# USB.net
KiCad netlist of a schematic drawn in Altium Designer
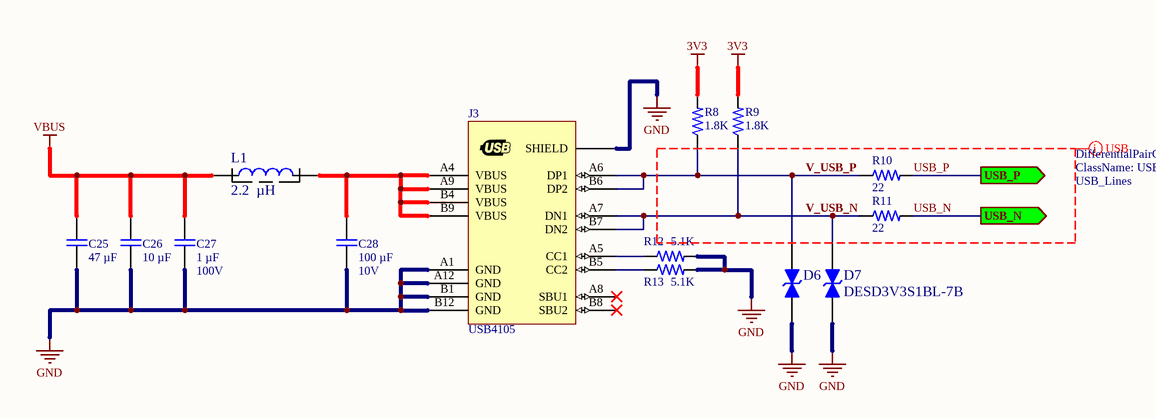
[diagram p0: USB.SchDoc]

(export (version "E")
  (design (tool "Eeschema 10.0.6"))
  (components
    (comp (ref "C25")
      (value "47 µF")
      (footprint "MergenElektronik_Capacitors_Ceramics_SMDs_1206_M_NS")
      (description "Mergen Elektronik - Capacitors - Ceramics - SMDs - 1206 - 47 µF - 25V")
      (fields (field (name "MANUFACTURER") "TDK Corporation") (field (name "TOLERANCE") "±20%"))
      (libsource (lib "MergenElektronik_Capacitors_Ceramics_SMDs") (part "MergenElektronik_Capacitors_Ceramic_SMDs_47µF_25V"))
    )
    (comp (ref "C26")
      (value "10 µF")
      (footprint "MergenElektronik_Capacitors_Ceramics_SMDs_0603_M_NS")
      (description "Mergen Elektronik - Capacitors - Ceramics - SMDs - 0603 - 10 µF - 25V")
      (fields (field (name "MANUFACTURER") "Murata Electronics") (field (name "TOLERANCE") "±20%"))
      (libsource (lib "MergenElektronik_Capacitors_Ceramics_SMDs") (part "MergenElektronik_Capacitors_Ceramic_SMDs_10µF_25V"))
    )
    (comp (ref "C27")
      (value "1 µF")
      (footprint "MergenElektronik_Capacitors_Ceramics_SMDs_1206_M_NS")
      (description "Mergen Elektronik - Capacitors - Ceramics - SMDs - 1206 - 1 µF - 100V")
      (fields
        (field (name "MANUFACTURER") "Samsung Electro-Mechanics")
        (field (name "TOLERANCE") "±10%")
        (field (name "VOLTAGE RATING") "100V")
      )
      (libsource (lib "MergenElektronik_Capacitors_Ceramics_SMDs") (part "MergenElektronik_Capacitors_Ceramic_SMDs_1µF_100V"))
    )
    (comp (ref "C28")
      (value "100 µF")
      (footprint "MergenElektronik_Capacitors_Ceramics_SMDs_1210_M_NS")
      (description "Mergen Elektronik - Capacitors - Ceramics - SMDs - 1210 - 100 µF - 10V")
      (fields
        (field (name "MANUFACTURER") "Samsung Electro-Mechanics")
        (field (name "TOLERANCE") "±20%")
        (field (name "VOLTAGE RATING") "10V")
      )
      (libsource (lib "MergenElektronik_Capacitors_Ceramics_SMDs") (part "MergenElektronik_Capacitors_Ceramic_SMDs_100µF_10V"))
    )
    (comp (ref "D6")
      (value "DESD3V3S1BL-7B")
      (footprint "MergenElektronik_Diodes_TVSDiodes_0402_L")
      (description "Mergen Elektronik - Diodes - TVS Diodes - DESD3V3S1BL-7B")
      (fields (field (name "MANUFACTURER") "Diodes Incorporated"))
      (libsource (lib "MergenElektronik_Diodes_TVSDiodes") (part "MergenElektronik_Diodes_TVSDiodes_DESD3V3S1BL-7B"))
    )
    (comp (ref "D7")
      (value "DESD3V3S1BL-7B")
      (footprint "MergenElektronik_Diodes_TVSDiodes_0402_L")
      (description "Mergen Elektronik - Diodes - TVS Diodes - DESD3V3S1BL-7B")
      (fields (field (name "MANUFACTURER") "Diodes Incorporated"))
      (libsource (lib "MergenElektronik_Diodes_TVSDiodes") (part "MergenElektronik_Diodes_TVSDiodes_DESD3V3S1BL-7B"))
    )
    (comp (ref "J3")
      (value "USB4105")
      (footprint "MergenElektronik_Connectors_USB_USB4105")
      (description "Mergen Elektronik - Connectors - USB Connectors - USB4105")
      (fields (field (name "MANUFACTURER") "GCT"))
      (libsource (lib "MergenElektronik_Connectors_USB") (part "MergenElektronik_Connectors_USB_USB4105"))
    )
    (comp (ref "L1")
      (value "2.2  µH")
      (footprint "MergenElektronik_Inductors_PowerInductors_SMDs_1008_M_NS")
      (description "Mergen Elektronik - Inductors - Power Inductors - SMDs - 1008 - 2.2 µh - 2A")
      (fields (field (name "MANUFACTURER") "Samsung Electro-Mechanics"))
      (libsource (lib "MergenElektronik_Inductors_PowerInductors_SMDs") (part "MergenElektronik_Inductors_PowerInductors_SMDs_1008_2.2µH-2A"))
    )
    (comp (ref "R8")
      (value "1.8K")
      (footprint "MergenElektronik_Resistors_ChipResistors_0603_M_NS")
      (description "Mergen Elektronik - Resistors - Chip Resistors - 0603 - 1.8K")
      (fields (field (name "MANUFACTURER") "Stackpole Electronics Inc") (field (name "POWER") "1/10W"))
      (libsource (lib "MergenElektronik_Resistors_ChipResistors") (part "MergenElektronik_Resistors_ChipResistors_0603_1.8K"))
    )
    (comp (ref "R9")
      (value "1.8K")
      (footprint "MergenElektronik_Resistors_ChipResistors_0603_M_NS")
      (description "Mergen Elektronik - Resistors - Chip Resistors - 0603 - 1.8K")
      (fields (field (name "MANUFACTURER") "Stackpole Electronics Inc") (field (name "POWER") "1/10W"))
      (libsource (lib "MergenElektronik_Resistors_ChipResistors") (part "MergenElektronik_Resistors_ChipResistors_0603_1.8K"))
    )
    (comp (ref "R10")
      (value "22")
      (footprint "MergenElektronik_Resistors_ChipResistors_0603_M_NS")
      (description "Mergen Elektronik - Resistors - Chip Resistors - 0603 - 22")
      (fields (field (name "MANUFACTURER") "TE Connectivity Passive Product") (field (name "POWER") "1/10W"))
      (libsource (lib "MergenElektronik_Resistors_ChipResistors") (part "MergenElektronik_Resistors_ChipResistors_0603_22"))
    )
    (comp (ref "R11")
      (value "22")
      (footprint "MergenElektronik_Resistors_ChipResistors_0603_M_NS")
      (description "Mergen Elektronik - Resistors - Chip Resistors - 0603 - 22")
      (fields (field (name "MANUFACTURER") "TE Connectivity Passive Product") (field (name "POWER") "1/10W"))
      (libsource (lib "MergenElektronik_Resistors_ChipResistors") (part "MergenElektronik_Resistors_ChipResistors_0603_22"))
    )
    (comp (ref "R12")
      (value "5.1K")
      (footprint "MergenElektronik_Resistors_ChipResistors_0603_M_NS")
      (description "Mergen Elektronik - Resistors - Chip Resistors - 0603 - 5.1K")
      (fields (field (name "MANUFACTURER") "Stackpole Electronics Inc") (field (name "POWER") "1/10W"))
      (libsource (lib "MergenElektronik_Resistors_ChipResistors") (part "MergenElektronik_Resistors_ChipResistors_0603_5.1K"))
    )
    (comp (ref "R13")
      (value "5.1K")
      (footprint "MergenElektronik_Resistors_ChipResistors_0603_M_NS")
      (description "Mergen Elektronik - Resistors - Chip Resistors - 0603 - 5.1K")
      (fields (field (name "MANUFACTURER") "Stackpole Electronics Inc") (field (name "POWER") "1/10W"))
      (libsource (lib "MergenElektronik_Resistors_ChipResistors") (part "MergenElektronik_Resistors_ChipResistors_0603_5.1K"))
    )
  )
  (nets
    (net (code "1") (name "/USB_N") (class "Default")
      (node (ref "R11") (pin "2") (pinfunction "2_2") (pintype "passive"))
    )
    (net (code "2") (name "/USB_P") (class "Default")
      (node (ref "R10") (pin "2") (pinfunction "2_2") (pintype "passive"))
    )
    (net (code "3") (name "/V_USB_N") (class "Default")
      (node (ref "D7") (pin "2") (pinfunction "KATOT_2") (pintype "passive"))
      (node (ref "J3") (pin "A7") (pinfunction "DN1_A7") (pintype "bidirectional"))
      (node (ref "J3") (pin "B7") (pinfunction "DN2_B7") (pintype "bidirectional"))
      (node (ref "R11") (pin "1") (pinfunction "1_1") (pintype "passive"))
      (node (ref "R9") (pin "1") (pinfunction "1_1") (pintype "passive"))
    )
    (net (code "4") (name "/V_USB_P") (class "Default")
      (node (ref "D6") (pin "2") (pinfunction "KATOT_2") (pintype "passive"))
      (node (ref "J3") (pin "A6") (pinfunction "DP1_A6") (pintype "bidirectional"))
      (node (ref "J3") (pin "B6") (pinfunction "DP2_B6") (pintype "bidirectional"))
      (node (ref "R10") (pin "1") (pinfunction "1_1") (pintype "passive"))
      (node (ref "R8") (pin "1") (pinfunction "1_1") (pintype "passive"))
    )
    (net (code "5") (name "3V3") (class "Default")
      (node (ref "R8") (pin "2") (pinfunction "2_2") (pintype "passive"))
      (node (ref "R9") (pin "2") (pinfunction "2_2") (pintype "passive"))
    )
    (net (code "6") (name "GND") (class "Default")
      (node (ref "C25") (pin "2") (pinfunction "2_2") (pintype "passive"))
      (node (ref "C26") (pin "2") (pinfunction "2_2") (pintype "passive"))
      (node (ref "C27") (pin "2") (pinfunction "2_2") (pintype "passive"))
      (node (ref "C28") (pin "2") (pinfunction "2_2") (pintype "passive"))
      (node (ref "D6") (pin "1") (pinfunction "ANOT_1") (pintype "passive"))
      (node (ref "D7") (pin "1") (pinfunction "ANOT_1") (pintype "passive"))
      (node (ref "J3") (pin "A1") (pinfunction "GND_A1") (pintype "power_in"))
      (node (ref "J3") (pin "A12") (pinfunction "GND_A12") (pintype "power_in"))
      (node (ref "J3") (pin "B1") (pinfunction "GND_B1") (pintype "power_in"))
      (node (ref "J3") (pin "B12") (pinfunction "GND_B12") (pintype "power_in"))
      (node (ref "J3") (pin "SHIELD") (pinfunction "SHIELD_SHIELD") (pintype "power_in"))
      (node (ref "R12") (pin "2") (pinfunction "2_2") (pintype "passive"))
      (node (ref "R13") (pin "2") (pinfunction "2_2") (pintype "passive"))
    )
    (net (code "7") (name "Net-(C28-Pad1)") (class "Default")
      (node (ref "C28") (pin "1") (pinfunction "1_1") (pintype "passive"))
      (node (ref "J3") (pin "A4") (pinfunction "VBUS_A4") (pintype "power_in"))
      (node (ref "J3") (pin "A9") (pinfunction "VBUS_A9") (pintype "passive"))
      (node (ref "J3") (pin "B4") (pinfunction "VBUS_B4") (pintype "power_in"))
      (node (ref "J3") (pin "B9") (pinfunction "VBUS_B9") (pintype "power_in"))
      (node (ref "L1") (pin "2") (pinfunction "2_2") (pintype "passive"))
    )
    (net (code "8") (name "Net-(J3-CC1)") (class "Default")
      (node (ref "J3") (pin "A5") (pinfunction "CC1_A5") (pintype "bidirectional"))
      (node (ref "R12") (pin "1") (pinfunction "1_1") (pintype "passive"))
    )
    (net (code "9") (name "Net-(J3-CC2)") (class "Default")
      (node (ref "J3") (pin "B5") (pinfunction "CC2_B5") (pintype "bidirectional"))
      (node (ref "R13") (pin "1") (pinfunction "1_1") (pintype "passive"))
    )
    (net (code "10") (name "VBUS") (class "Default")
      (node (ref "C25") (pin "1") (pinfunction "1_1") (pintype "passive"))
      (node (ref "C26") (pin "1") (pinfunction "1_1") (pintype "passive"))
      (node (ref "C27") (pin "1") (pinfunction "1_1") (pintype "passive"))
      (node (ref "L1") (pin "1") (pinfunction "1_1") (pintype "passive"))
    )
    (net (code "11") (name "unconnected-(J3-SBU1-PadA8)") (class "Default")
      (node (ref "J3") (pin "A8") (pinfunction "SBU1_A8") (pintype "bidirectional+no_connect"))
    )
    (net (code "12") (name "unconnected-(J3-SBU2-PadB8)") (class "Default")
      (node (ref "J3") (pin "B8") (pinfunction "SBU2_B8") (pintype "bidirectional+no_connect"))
    )
  )
)
